# DoorSensor-Remote_Lora.net
KiCad netlist of a schematic drawn in Altium Designer
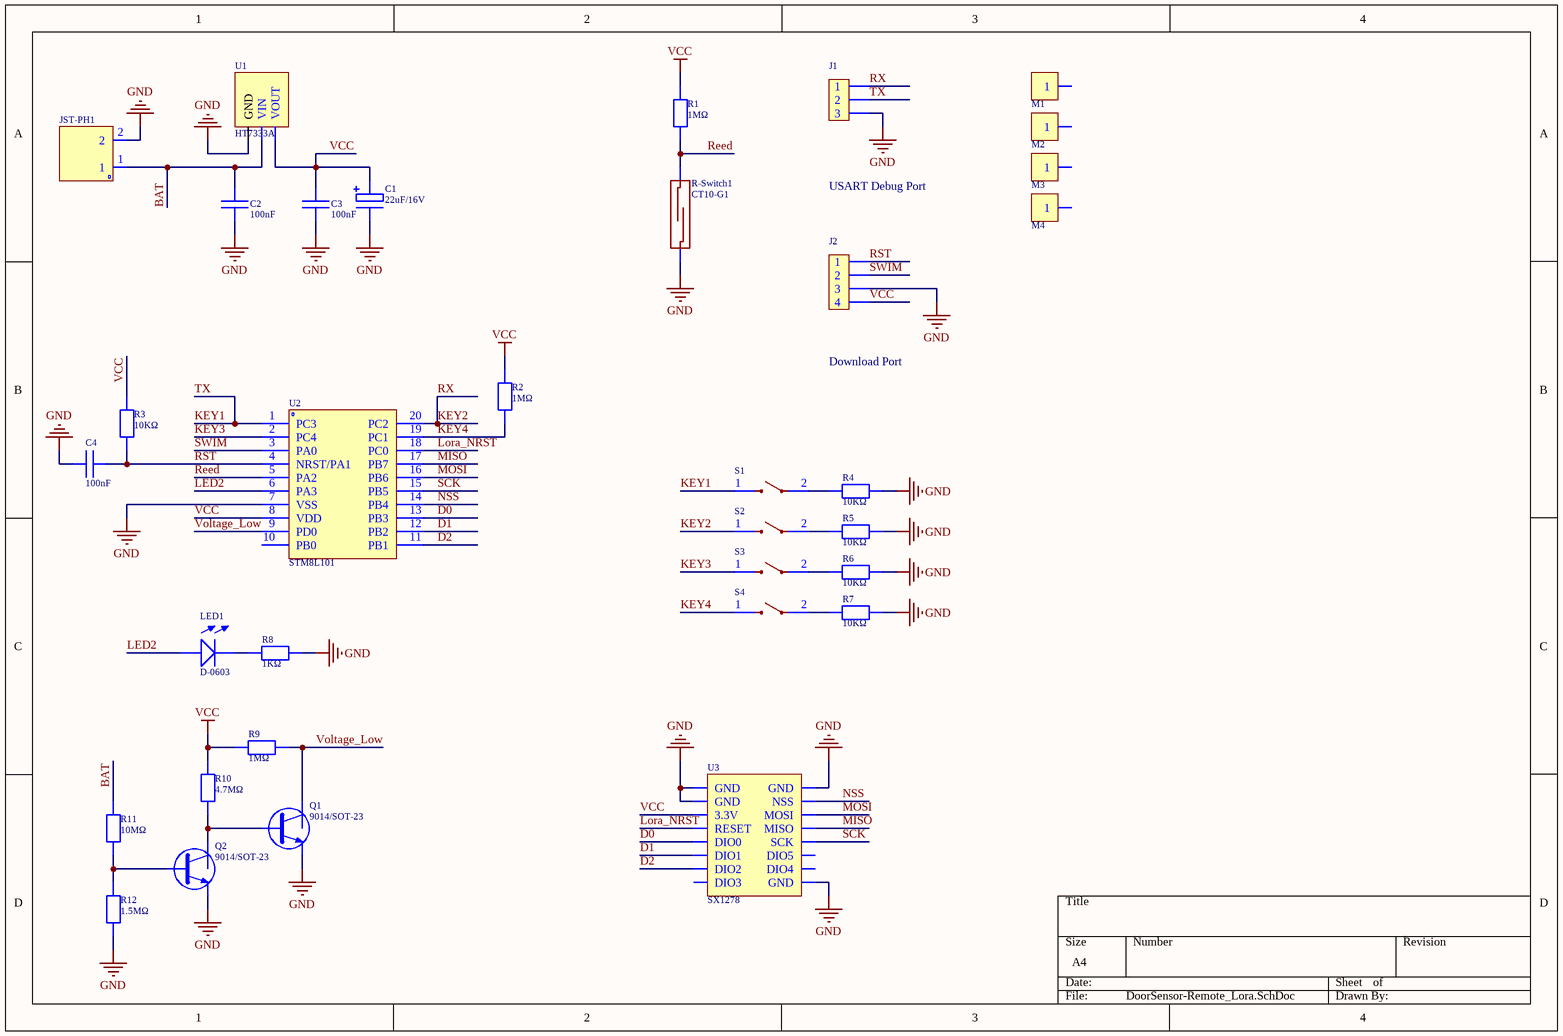
[diagram p0: DoorSensor-Remote_Lora.SchDoc]

(export (version "E")
  (design (tool "Eeschema 10.0.6"))
  (components
    (comp (ref "C1")
      (value "22uF/16V")
      (footprint "C(Electrolytic)_SMD-D4.0mm_L5.4mm")
      (libsource (lib "Schematic Library_General") (part "Capacitor_Electrolytic-SMD-D4.0xL5.4mm"))
    )
    (comp (ref "C2")
      (value "100nF")
      (footprint "C0603")
      (libsource (lib "Schematic Library_General") (part "Capacitor_0603"))
    )
    (comp (ref "C3")
      (value "100nF")
      (footprint "C0603")
      (libsource (lib "Schematic Library_General") (part "Capacitor_0603"))
    )
    (comp (ref "C4")
      (value "100nF")
      (footprint "C0603")
      (libsource (lib "Schematic Library_General") (part "Capacitor_0603"))
    )
    (comp (ref "J1")
      (value "PinHeader_3Pin")
      (footprint "PinHeader_3Pin-2.54mm")
      (description "Straight Single Row, Square Pitch, 2.54mm")
      (libsource (lib "Schematic Library_General") (part "PinHeader_3Pin"))
    )
    (comp (ref "J2")
      (value "PinHeader_4Pin")
      (footprint "PinHeader_4Pin-2.54mm")
      (description "Straight Single Row, Square Pitch, 2.54mm")
      (libsource (lib "Schematic Library_General") (part "PinHeader_4Pin"))
    )
    (comp (ref "JST-PH1")
      (value "JST-PH2.0_2Pin-TH-Vertical")
      (footprint "Connector-JST-PH2.0-2Pin_TH-Vertical")
      (libsource (lib "Schematic Library_General") (part "JST-PH2.0_2Pin-TH-Vertical"))
    )
    (comp (ref "LED1")
      (value "D-0603")
      (footprint "LED0603-Castellated")
      (libsource (lib "Schematic Library_General") (part "LED_0603"))
    )
    (comp (ref "M1")
      (value "PCB Mounting Hole")
      (footprint "PCB Mounting Hole")
      (description "Mounting Hole")
      (libsource (lib "Schematic Library_General") (part "PCB Mounting Hole"))
    )
    (comp (ref "M2")
      (value "PCB Mounting Hole")
      (footprint "PCB Mounting Hole")
      (description "Mounting Hole")
      (libsource (lib "Schematic Library_General") (part "PCB Mounting Hole"))
    )
    (comp (ref "M3")
      (value "PCB Mounting Hole")
      (footprint "PCB Mounting Hole")
      (description "Mounting Hole")
      (libsource (lib "Schematic Library_General") (part "PCB Mounting Hole"))
    )
    (comp (ref "M4")
      (value "PCB Mounting Hole")
      (footprint "PCB Mounting Hole")
      (description "Mounting Hole")
      (libsource (lib "Schematic Library_General") (part "PCB Mounting Hole"))
    )
    (comp (ref "Q1")
      (value "9014/SOT-23")
      (footprint "SOT-23-3")
      (libsource (lib "Schematic Library_General") (part "NPN_SOT-23-3"))
    )
    (comp (ref "Q2")
      (value "9014/SOT-23")
      (footprint "SOT-23-3")
      (libsource (lib "Schematic Library_General") (part "NPN_SOT-23-3"))
    )
    (comp (ref "R-Switch1")
      (value "CT10-G1")
      (footprint "Reed Switch_Molded-SMD_SPST")
      (libsource (lib "Schematic Library_General") (part "Reed-Switch_Molded-SMD"))
    )
    (comp (ref "R1")
      (value "1MΩ")
      (footprint "R0603")
      (libsource (lib "Schematic Library_General") (part "Resistor_0603"))
    )
    (comp (ref "R2")
      (value "1MΩ")
      (footprint "R0603")
      (libsource (lib "Schematic Library_General") (part "Resistor_0603"))
    )
    (comp (ref "R3")
      (value "10KΩ")
      (footprint "R0805")
      (libsource (lib "Schematic Library_General") (part "Resistor_0805"))
    )
    (comp (ref "R4") (value "10KΩ") (footprint "R0603") (libsource (lib "") (part "Resistor_0603_1")))
    (comp (ref "R5") (value "10KΩ") (footprint "R0603") (libsource (lib "") (part "Resistor_0603_1")))
    (comp (ref "R6") (value "10KΩ") (footprint "R0603") (libsource (lib "") (part "Resistor_0603_1")))
    (comp (ref "R7") (value "10KΩ") (footprint "R0603") (libsource (lib "") (part "Resistor_0603_1")))
    (comp (ref "R8") (value "1KΩ") (footprint "R0603") (libsource (lib "") (part "Resistor_0603_1")))
    (comp (ref "R9") (value "1MΩ") (footprint "R0603") (libsource (lib "") (part "Resistor_0603_1")))
    (comp (ref "R10")
      (value "4.7MΩ")
      (footprint "R0603")
      (libsource (lib "Schematic Library_General") (part "Resistor_0603"))
    )
    (comp (ref "R11")
      (value "10MΩ")
      (footprint "R0603")
      (libsource (lib "Schematic Library_General") (part "Resistor_0603"))
    )
    (comp (ref "R12")
      (value "1.5MΩ")
      (footprint "R0603")
      (libsource (lib "Schematic Library_General") (part "Resistor_0603"))
    )
    (comp (ref "S1")
      (value "CK_RS282G05A3")
      (footprint "Tactile Button_SMD-SPST_L6.1-W3.7-H2.5")
      (libsource (lib "Schematic Library_General") (part "Button_Push_2Pin_SMD"))
    )
    (comp (ref "S2")
      (value "CK_RS282G05A3")
      (footprint "Tactile Button_SMD-SPST_L6.1-W3.7-H2.5")
      (libsource (lib "Schematic Library_General") (part "Button_Push_2Pin_SMD"))
    )
    (comp (ref "S3")
      (value "CK_RS282G05A3")
      (footprint "Tactile Button_SMD-SPST_L6.1-W3.7-H2.5")
      (libsource (lib "Schematic Library_General") (part "Button_Push_2Pin_SMD"))
    )
    (comp (ref "S4")
      (value "CK_RS282G05A3")
      (footprint "Tactile Button_SMD-SPST_L6.1-W3.7-H2.5")
      (libsource (lib "Schematic Library_General") (part "Button_Push_2Pin_SMD"))
    )
    (comp (ref "U1")
      (value "HT7333A")
      (footprint "SOT89-3")
      (libsource (lib "Schematic Library_General") (part "LDO_SOT89-3"))
    )
    (comp (ref "U2")
      (value "STM8L101")
      (footprint "TSSOP-20_4.4x6.5mm_P0.65mm")
      (description "4.4x6.5mm_P0.65mm")
      (libsource (lib "Schematic Library_General") (part "STM8L101_TSSOP-20"))
    )
    (comp (ref "U3")
      (value "SX1278")
      (footprint "SX1278_Ra-02-Lora Module_17x16mm")
      (description "17x16mm")
      (libsource (lib "Schematic Library_General") (part "SX1278_Ra-02-Lora Module"))
    )
  )
  (nets
    (net (code "1") (name "/BAT") (class "Default")
      (node (ref "C2") (pin "2") (pintype "passive"))
      (node (ref "JST-PH1") (pin "1") (pinfunction "1_1") (pintype "passive"))
      (node (ref "R11") (pin "2") (pintype "passive"))
      (node (ref "U1") (pin "2") (pinfunction "VIN_2") (pintype "passive"))
    )
    (net (code "2") (name "/D0") (class "Default")
      (node (ref "U2") (pin "13") (pinfunction "PB3_13") (pintype "passive"))
      (node (ref "U3") (pin "5") (pinfunction "DIO0_5") (pintype "passive"))
    )
    (net (code "3") (name "/D1") (class "Default")
      (node (ref "U2") (pin "12") (pinfunction "PB2_12") (pintype "passive"))
      (node (ref "U3") (pin "6") (pinfunction "DIO1_6") (pintype "passive"))
    )
    (net (code "4") (name "/D2") (class "Default")
      (node (ref "U2") (pin "11") (pinfunction "PB1_11") (pintype "passive"))
      (node (ref "U3") (pin "7") (pinfunction "DIO2_7") (pintype "passive"))
    )
    (net (code "5") (name "/KEY1") (class "Default")
      (node (ref "J1") (pin "2") (pinfunction "2_2") (pintype "passive"))
      (node (ref "S1") (pin "1") (pintype "passive"))
      (node (ref "U2") (pin "1") (pinfunction "PC3_1") (pintype "passive"))
    )
    (net (code "6") (name "/KEY2") (class "Default")
      (node (ref "J1") (pin "1") (pinfunction "1_1") (pintype "passive"))
      (node (ref "S2") (pin "1") (pintype "passive"))
      (node (ref "U2") (pin "20") (pinfunction "PC2_20") (pintype "passive"))
    )
    (net (code "7") (name "/KEY3") (class "Default")
      (node (ref "S3") (pin "1") (pintype "passive"))
      (node (ref "U2") (pin "2") (pinfunction "PC4_2") (pintype "passive"))
    )
    (net (code "8") (name "/KEY4") (class "Default")
      (node (ref "R2") (pin "1") (pintype "passive"))
      (node (ref "S4") (pin "1") (pintype "passive"))
      (node (ref "U2") (pin "19") (pinfunction "PC1_19") (pintype "passive"))
    )
    (net (code "9") (name "/LED2") (class "Default")
      (node (ref "LED1") (pin "1") (pintype "passive"))
      (node (ref "U2") (pin "6") (pinfunction "PA3_6") (pintype "passive"))
    )
    (net (code "10") (name "/Lora_NRST") (class "Default")
      (node (ref "U2") (pin "18") (pinfunction "PC0_18") (pintype "passive"))
      (node (ref "U3") (pin "4") (pinfunction "RESET_4") (pintype "passive"))
    )
    (net (code "11") (name "/MISO") (class "Default")
      (node (ref "U2") (pin "17") (pinfunction "PB7_17") (pintype "passive"))
      (node (ref "U3") (pin "13") (pinfunction "MISO_13") (pintype "passive"))
    )
    (net (code "12") (name "/MOSI") (class "Default")
      (node (ref "U2") (pin "16") (pinfunction "PB6_16") (pintype "passive"))
      (node (ref "U3") (pin "14") (pinfunction "MOSI_14") (pintype "passive"))
    )
    (net (code "13") (name "/NSS") (class "Default")
      (node (ref "U2") (pin "14") (pinfunction "PB4_14") (pintype "passive"))
      (node (ref "U3") (pin "15") (pinfunction "NSS_15") (pintype "passive"))
    )
    (net (code "14") (name "/RST") (class "Default")
      (node (ref "C4") (pin "2") (pintype "passive"))
      (node (ref "J2") (pin "1") (pinfunction "1_1") (pintype "passive"))
      (node (ref "R3") (pin "1") (pintype "passive"))
      (node (ref "U2") (pin "4") (pinfunction "NRST/PA1_4") (pintype "passive"))
    )
    (net (code "15") (name "/Reed") (class "Default")
      (node (ref "R-Switch1") (pin "2") (pintype "passive"))
      (node (ref "R1") (pin "1") (pintype "passive"))
      (node (ref "U2") (pin "5") (pinfunction "PA2_5") (pintype "passive"))
    )
    (net (code "16") (name "/SCK") (class "Default")
      (node (ref "U2") (pin "15") (pinfunction "PB5_15") (pintype "passive"))
      (node (ref "U3") (pin "12") (pinfunction "SCK_12") (pintype "passive"))
    )
    (net (code "17") (name "/SWIM") (class "Default")
      (node (ref "J2") (pin "2") (pinfunction "2_2") (pintype "passive"))
      (node (ref "U2") (pin "3") (pinfunction "PA0_3") (pintype "passive"))
    )
    (net (code "18") (name "/Voltage_Low") (class "Default")
      (node (ref "Q1") (pin "3") (pintype "passive"))
      (node (ref "R9") (pin "2") (pintype "passive"))
      (node (ref "U2") (pin "9") (pinfunction "PD0_9") (pintype "passive"))
    )
    (net (code "19") (name "GND") (class "Default")
      (node (ref "C1") (pin "2") (pintype "passive"))
      (node (ref "C2") (pin "1") (pintype "passive"))
      (node (ref "C3") (pin "1") (pintype "passive"))
      (node (ref "C4") (pin "1") (pintype "passive"))
      (node (ref "J1") (pin "3") (pinfunction "3_3") (pintype "passive"))
      (node (ref "J2") (pin "3") (pinfunction "3_3") (pintype "passive"))
      (node (ref "JST-PH1") (pin "2") (pinfunction "2_2") (pintype "passive"))
      (node (ref "Q1") (pin "2") (pintype "passive"))
      (node (ref "Q2") (pin "2") (pintype "passive"))
      (node (ref "R-Switch1") (pin "1") (pintype "passive"))
      (node (ref "R12") (pin "1") (pintype "passive"))
      (node (ref "R4") (pin "2") (pintype "passive"))
      (node (ref "R5") (pin "2") (pintype "passive"))
      (node (ref "R6") (pin "2") (pintype "passive"))
      (node (ref "R7") (pin "2") (pintype "passive"))
      (node (ref "R8") (pin "2") (pintype "passive"))
      (node (ref "U1") (pin "1") (pinfunction "GND_1") (pintype "passive"))
      (node (ref "U2") (pin "7") (pinfunction "VSS_7") (pintype "passive"))
      (node (ref "U3") (pin "1") (pinfunction "GND_1") (pintype "passive"))
      (node (ref "U3") (pin "16") (pinfunction "GND_16") (pintype "passive"))
      (node (ref "U3") (pin "2") (pinfunction "GND_2") (pintype "passive"))
      (node (ref "U3") (pin "9") (pinfunction "GND_9") (pintype "passive"))
    )
    (net (code "20") (name "Net-(LED1-Pad2)") (class "Default")
      (node (ref "LED1") (pin "2") (pintype "passive"))
      (node (ref "R8") (pin "1") (pintype "passive"))
    )
    (net (code "21") (name "Net-(Q1-Pad1)") (class "Default")
      (node (ref "Q1") (pin "1") (pintype "passive"))
      (node (ref "Q2") (pin "3") (pintype "passive"))
      (node (ref "R10") (pin "1") (pintype "passive"))
    )
    (net (code "22") (name "Net-(Q2-Pad1)") (class "Default")
      (node (ref "Q2") (pin "1") (pintype "passive"))
      (node (ref "R11") (pin "1") (pintype "passive"))
      (node (ref "R12") (pin "2") (pintype "passive"))
    )
    (net (code "23") (name "Net-(R4-Pad1)") (class "Default")
      (node (ref "R4") (pin "1") (pintype "passive"))
      (node (ref "S1") (pin "2") (pintype "passive"))
    )
    (net (code "24") (name "Net-(R5-Pad1)") (class "Default")
      (node (ref "R5") (pin "1") (pintype "passive"))
      (node (ref "S2") (pin "2") (pintype "passive"))
    )
    (net (code "25") (name "Net-(R6-Pad1)") (class "Default")
      (node (ref "R6") (pin "1") (pintype "passive"))
      (node (ref "S3") (pin "2") (pintype "passive"))
    )
    (net (code "26") (name "Net-(R7-Pad1)") (class "Default")
      (node (ref "R7") (pin "1") (pintype "passive"))
      (node (ref "S4") (pin "2") (pintype "passive"))
    )
    (net (code "27") (name "VCC") (class "Default")
      (node (ref "C1") (pin "1") (pintype "passive"))
      (node (ref "C3") (pin "2") (pintype "passive"))
      (node (ref "J2") (pin "4") (pinfunction "4_4") (pintype "passive"))
      (node (ref "R1") (pin "2") (pintype "passive"))
      (node (ref "R10") (pin "2") (pintype "passive"))
      (node (ref "R2") (pin "2") (pintype "passive"))
      (node (ref "R3") (pin "2") (pintype "passive"))
      (node (ref "R9") (pin "1") (pintype "passive"))
      (node (ref "U1") (pin "3") (pinfunction "VOUT_3") (pintype "passive"))
      (node (ref "U2") (pin "8") (pinfunction "VDD_8") (pintype "passive"))
      (node (ref "U3") (pin "3") (pinfunction "3.3V_3") (pintype "passive"))
    )
    (net (code "28") (name "unconnected-(M1-Pad1)") (class "Default")
      (node (ref "M1") (pin "1") (pinfunction "1_1") (pintype "passive"))
    )
    (net (code "29") (name "unconnected-(M2-Pad1)") (class "Default")
      (node (ref "M2") (pin "1") (pinfunction "1_1") (pintype "passive"))
    )
    (net (code "30") (name "unconnected-(M3-Pad1)") (class "Default")
      (node (ref "M3") (pin "1") (pinfunction "1_1") (pintype "passive"))
    )
    (net (code "31") (name "unconnected-(M4-Pad1)") (class "Default")
      (node (ref "M4") (pin "1") (pinfunction "1_1") (pintype "passive"))
    )
    (net (code "32") (name "unconnected-(U2-PB0-Pad10)") (class "Default")
      (node (ref "U2") (pin "10") (pinfunction "PB0_10") (pintype "passive"))
    )
    (net (code "33") (name "unconnected-(U3-DIO3-Pad8)") (class "Default")
      (node (ref "U3") (pin "8") (pinfunction "DIO3_8") (pintype "passive"))
    )
    (net (code "34") (name "unconnected-(U3-DIO4-Pad10)") (class "Default")
      (node (ref "U3") (pin "10") (pinfunction "DIO4_10") (pintype "passive"))
    )
    (net (code "35") (name "unconnected-(U3-DIO5-Pad11)") (class "Default")
      (node (ref "U3") (pin "11") (pinfunction "DIO5_11") (pintype "passive"))
    )
  )
)
